# Redhat-Slate.net
KiCad netlist of a schematic drawn in EAGLE
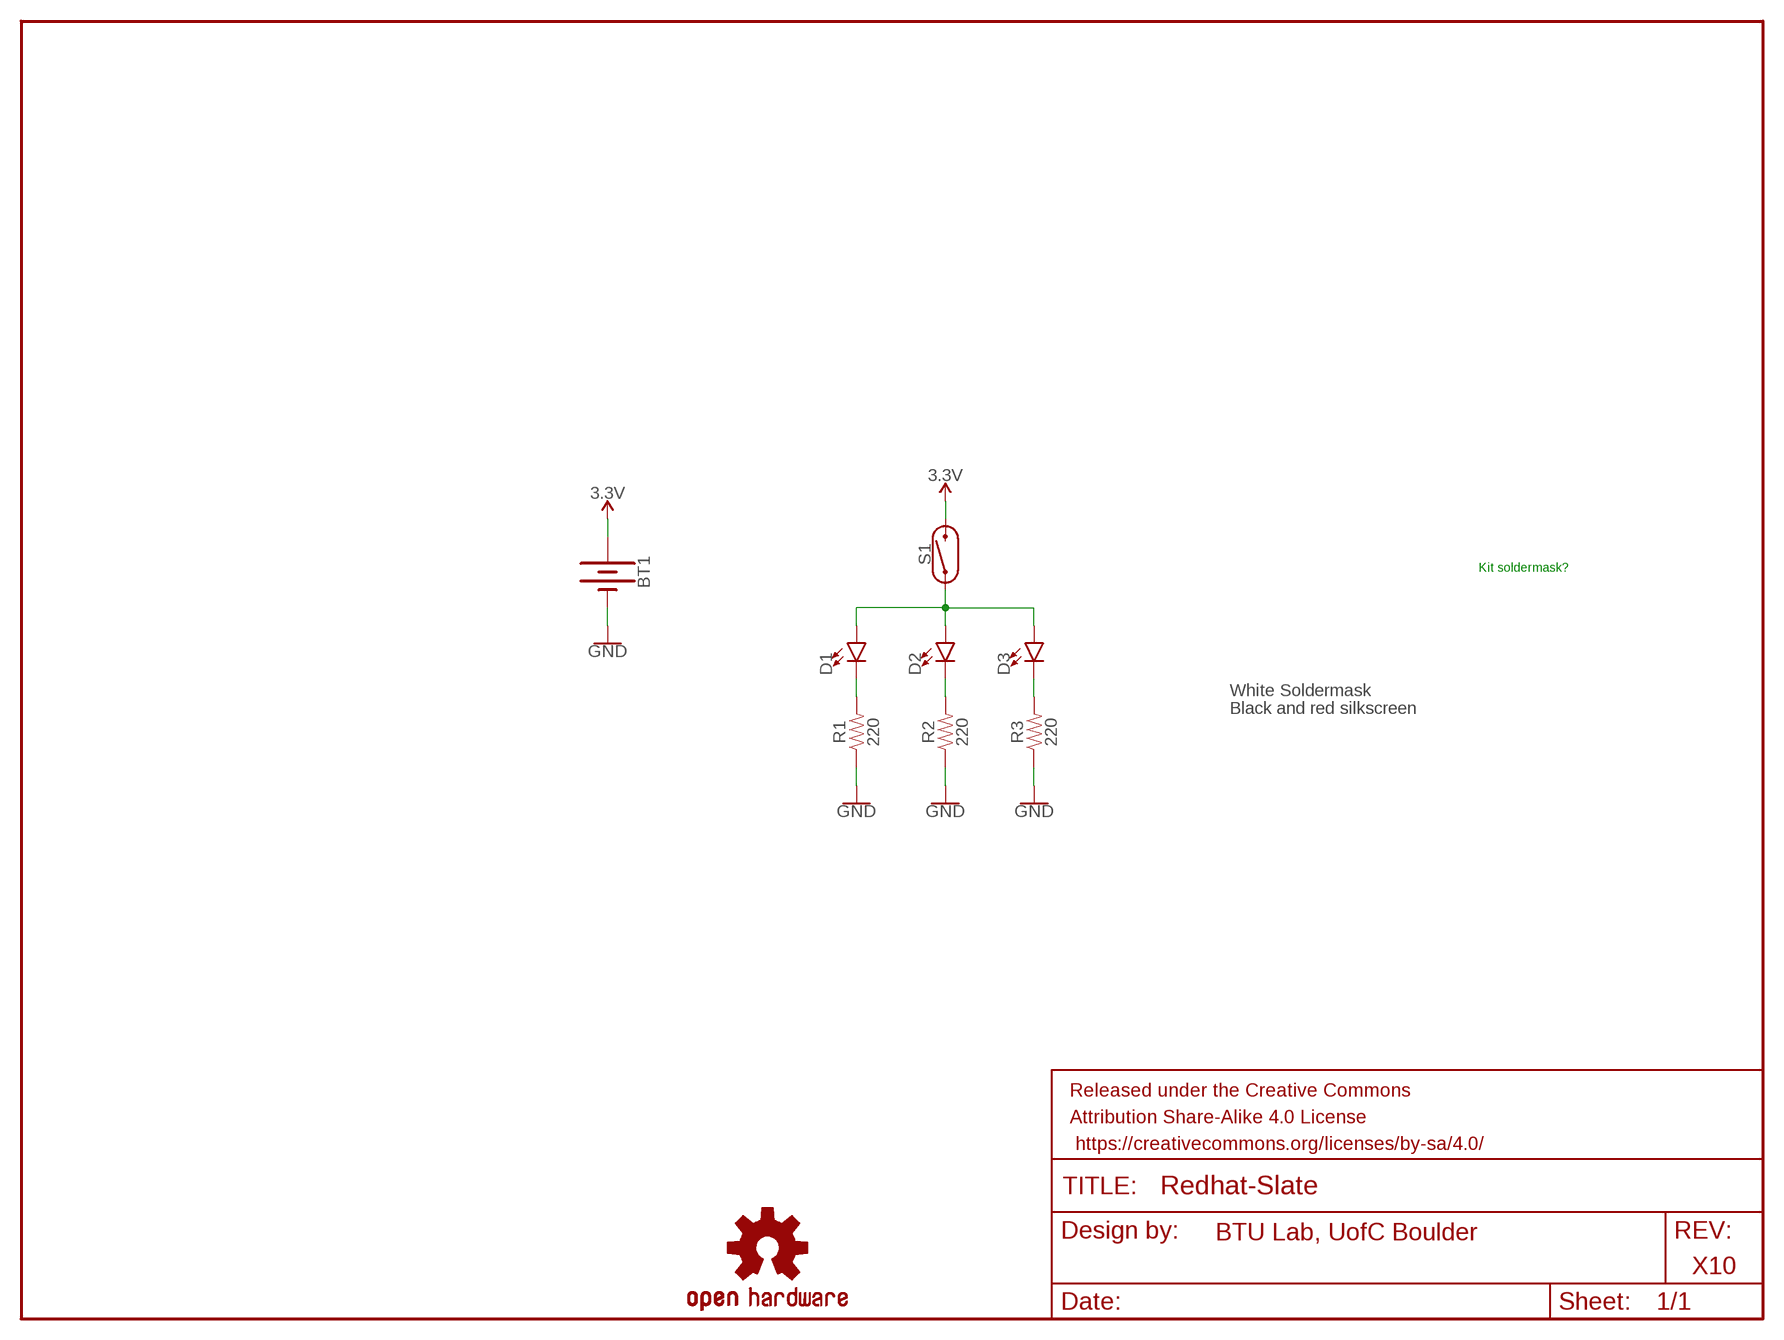
[diagram p0: schematic, sheet 1]

(export (version "E")
  (design (tool "Eeschema 10.0.6"))
  (components
    (comp (ref "BT1")
      (value "BATTERY-20MM_PTH")
      (footprint "eagle-import:BATTCOM_20MM_PTH")
      (libsource (lib "eagle-import") (part "BATTERY-20MM_PTH"))
    )
    (comp (ref "D1")
      (value "LEDRED")
      (footprint "eagle-import:LED_5MM_EXTRASILK")
      (libsource (lib "eagle-import") (part "LEDRED"))
    )
    (comp (ref "D2")
      (value "LEDRED")
      (footprint "eagle-import:LED_5MM_EXTRASILK")
      (libsource (lib "eagle-import") (part "LEDRED"))
    )
    (comp (ref "D3")
      (value "LEDRED")
      (footprint "eagle-import:LED_5MM_EXTRASILK")
      (libsource (lib "eagle-import") (part "LEDRED"))
    )
    (comp (ref "FRAME1")
      (value "FRAME-LETTER")
      (footprint "eagle-import:CREATIVE_COMMONS")
      (libsource (lib "eagle-import") (part "FRAME-LETTER"))
    )
    (comp (ref "LOGO4")
      (value "OSHW-LOGOS")
      (footprint "eagle-import:OSHW-LOGO-S")
      (libsource (lib "eagle-import") (part "OSHW-LOGOS"))
    )
    (comp (ref "R1")
      (value "220")
      (footprint "eagle-import:AXIAL-0.3")
      (libsource (lib "eagle-import") (part "1KOHM-HORIZ-1/4W-1%"))
    )
    (comp (ref "R2")
      (value "220")
      (footprint "eagle-import:AXIAL-0.3")
      (libsource (lib "eagle-import") (part "1KOHM-HORIZ-1/4W-1%"))
    )
    (comp (ref "R3")
      (value "220")
      (footprint "eagle-import:AXIAL-0.3")
      (libsource (lib "eagle-import") (part "1KOHM-HORIZ-1/4W-1%"))
    )
    (comp (ref "S1")
      (value "REED_SWITCH-PTH-INSULATED")
      (footprint "eagle-import:REED_SWITCH_PLASTIC")
      (libsource (lib "eagle-import") (part "REED_SWITCH-PTH-INSULATED"))
    )
  )
  (nets
    (net (code "1") (name "3.3V") (class "Default")
      (node (ref "BT1") (pin "1") (pinfunction "+_1") (pintype "power_in"))
      (node (ref "S1") (pin "P$2") (pinfunction "2_P$2") (pintype "passive"))
    )
    (net (code "2") (name "GND") (class "Default")
      (node (ref "BT1") (pin "2") (pinfunction "-_2") (pintype "power_in"))
      (node (ref "R1") (pin "P$1") (pinfunction "1_P$1") (pintype "passive"))
      (node (ref "R2") (pin "P$1") (pinfunction "1_P$1") (pintype "passive"))
      (node (ref "R3") (pin "P$1") (pinfunction "1_P$1") (pintype "passive"))
    )
    (net (code "3") (name "Net-(D1-C)") (class "Default")
      (node (ref "D1") (pin "K") (pinfunction "C_K") (pintype "passive"))
      (node (ref "R1") (pin "P$2") (pinfunction "2_P$2") (pintype "passive"))
    )
    (net (code "4") (name "Net-(D2-C)") (class "Default")
      (node (ref "D2") (pin "K") (pinfunction "C_K") (pintype "passive"))
      (node (ref "R2") (pin "P$2") (pinfunction "2_P$2") (pintype "passive"))
    )
    (net (code "5") (name "Net-(D3-C)") (class "Default")
      (node (ref "D3") (pin "K") (pinfunction "C_K") (pintype "passive"))
      (node (ref "R3") (pin "P$2") (pinfunction "2_P$2") (pintype "passive"))
    )
    (net (code "6") (name "Net-(S1-1)") (class "Default")
      (node (ref "D1") (pin "A") (pinfunction "A_A") (pintype "passive"))
      (node (ref "D2") (pin "A") (pinfunction "A_A") (pintype "passive"))
      (node (ref "D3") (pin "A") (pinfunction "A_A") (pintype "passive"))
      (node (ref "S1") (pin "P$1") (pinfunction "1_P$1") (pintype "passive"))
    )
  )
)
